# Delay.net
KiCad netlist of a schematic drawn in Altium Designer
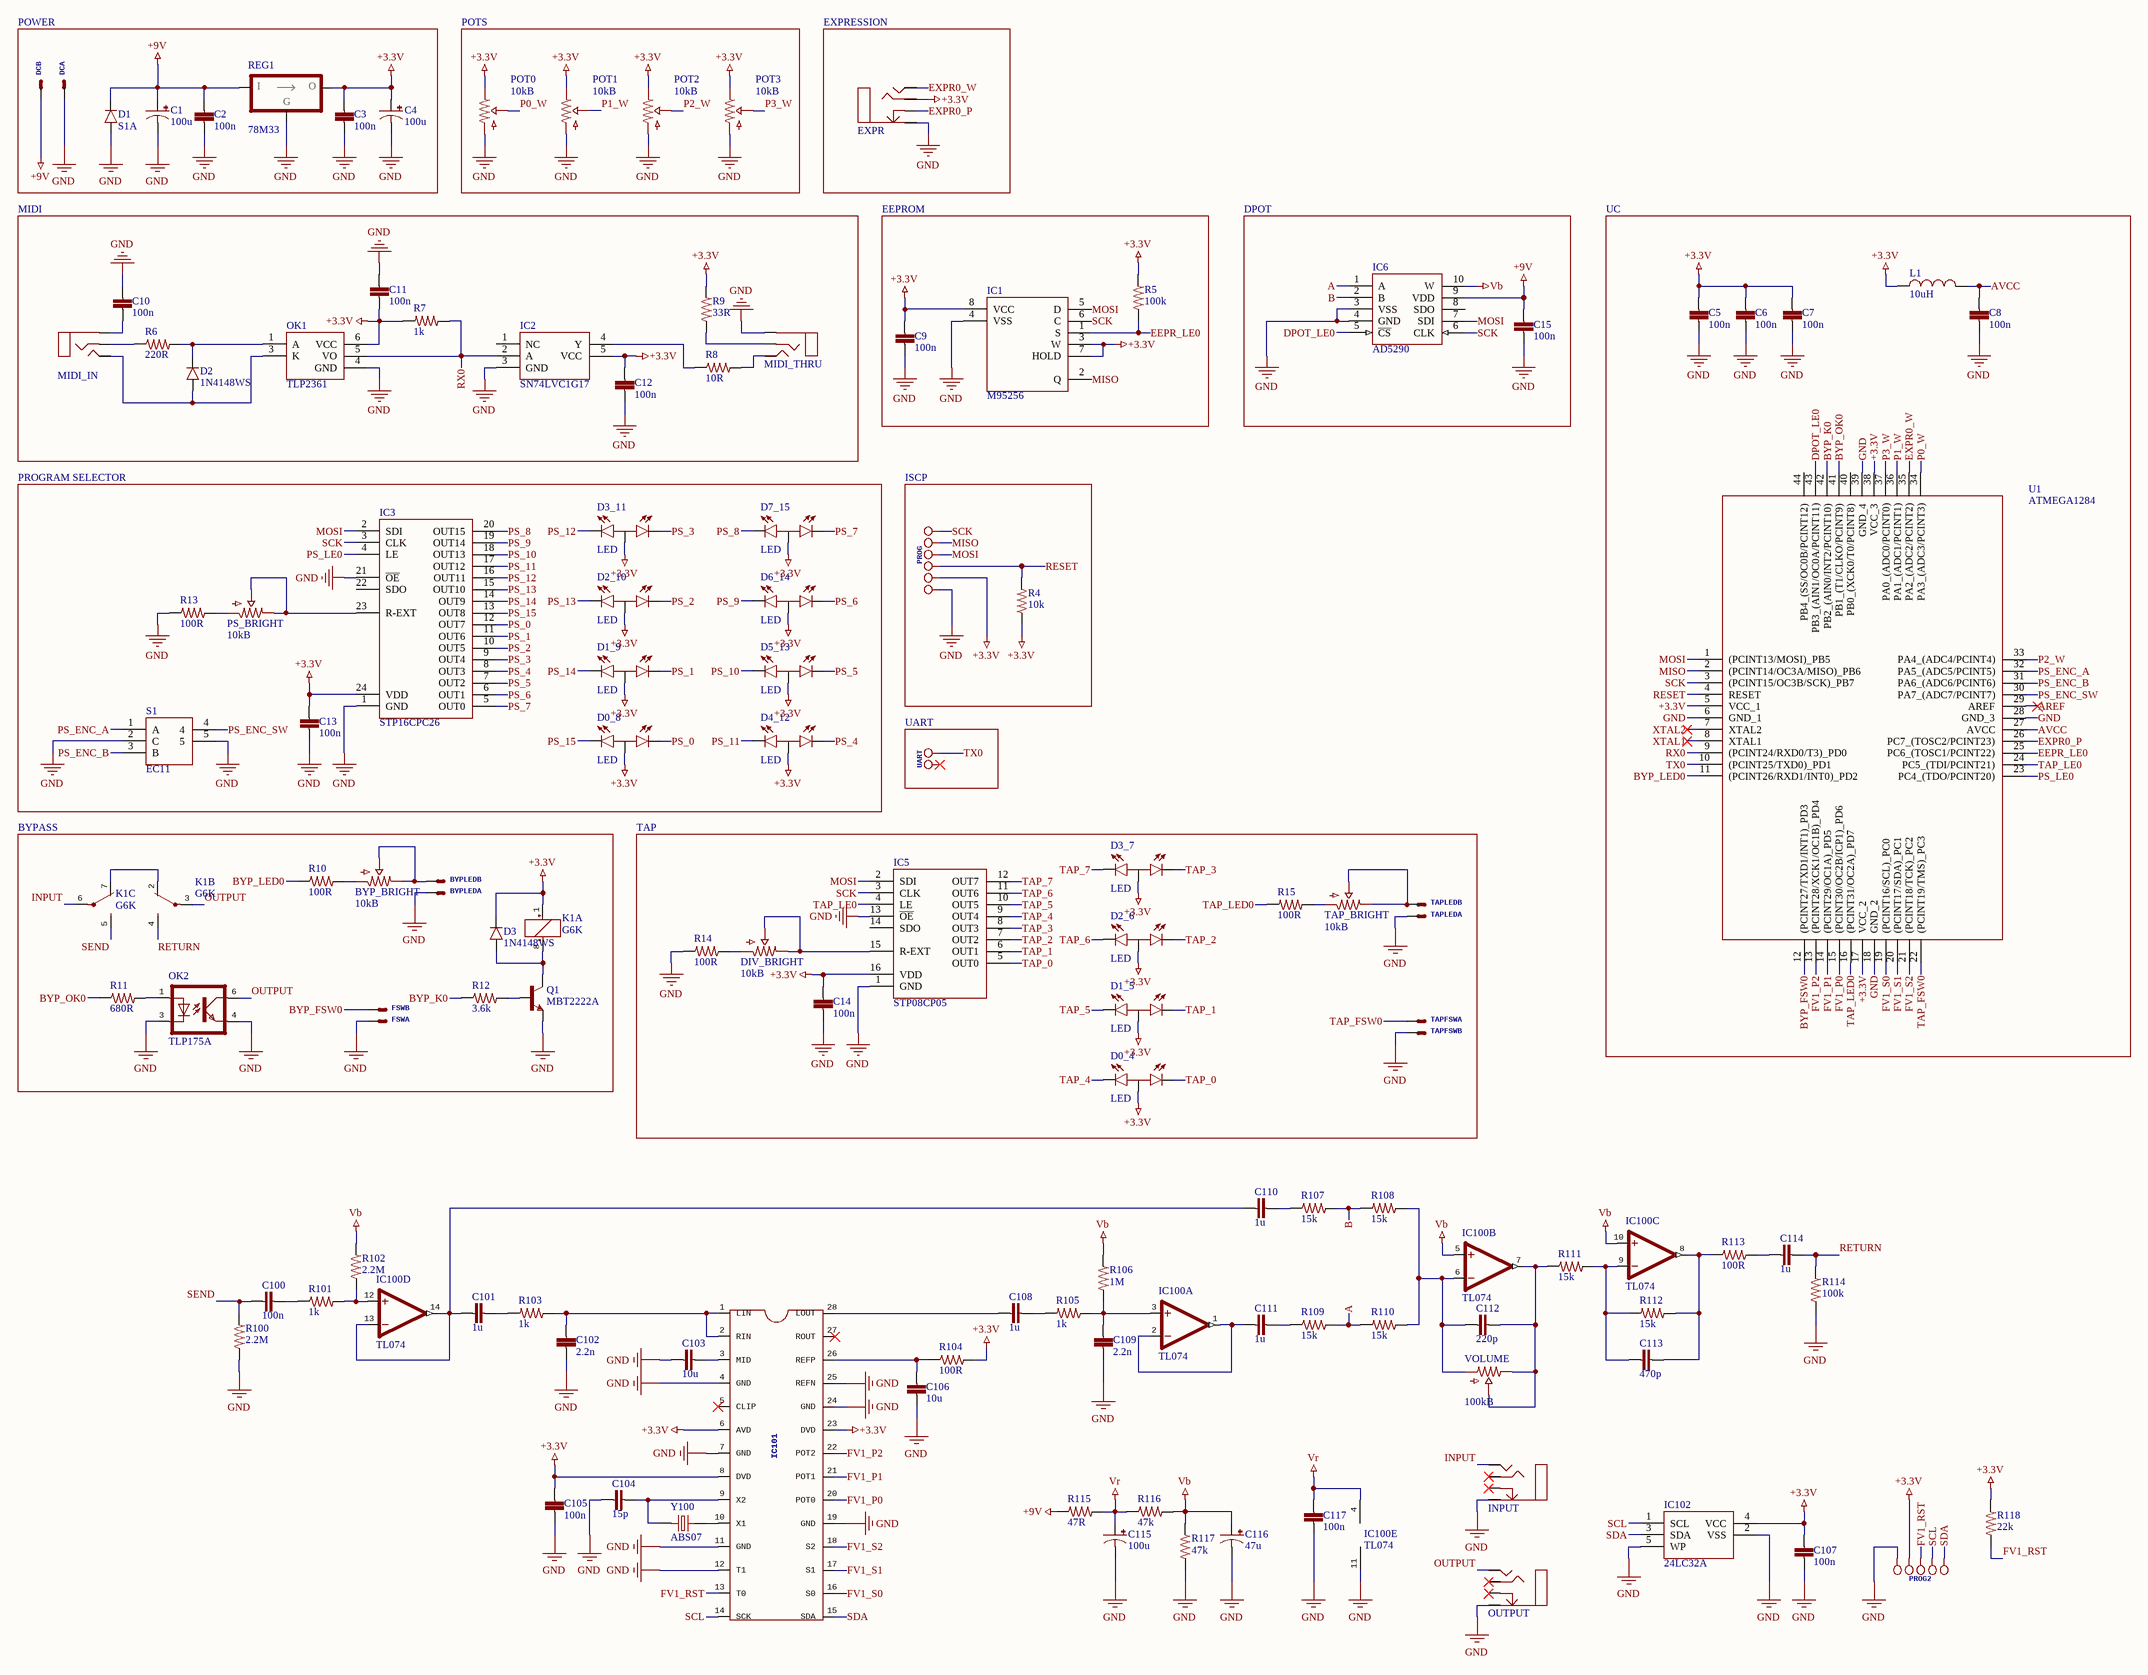
[diagram p0: Delay.SchDoc]

(export (version "E")
  (design (tool "Eeschema 10.0.6"))
  (components
    (comp (ref "BYPLED")
      (value "~")
      (footprint "JST-XH-02")
      (description "2 Pins male XH header")
      (libsource (lib "Pedals") (part "JST-XH-02"))
    )
    (comp (ref "BYP_BRIGHT")
      (value "10kB")
      (footprint "BOURNS_3362P")
      (description "10k Lin 3362P trimmer")
      (libsource (lib "Pedals") (part "TRIM_10kB_3362P"))
    )
    (comp (ref "C1")
      (value "100u")
      (footprint "CAPAE_D")
      (description "CAP ALUM 100UF 25V SMD")
      (fields
        (field (name "MANUFACTURER") "Multicomp")
        (field (name "MANUFACTURER PART NUMBER") "MCVVT025M101EA6L")
      )
      (libsource (lib "Pedals SMD") (part "MCVVT025M101EA6L"))
    )
    (comp (ref "C2")
      (value "100n")
      (footprint "CHIP_0603")
      (description "CAP CER 100NF 50V X7R 0603")
      (fields
        (field (name "MANUFACTURER") "Multicomp")
        (field (name "MANUFACTURER PART NUMBER") "MC0603B104K500CT")
      )
      (libsource (lib "") (part "MC0603B104K500CT_2"))
    )
    (comp (ref "C3")
      (value "100n")
      (footprint "CHIP_0603")
      (description "CAP CER 100NF 50V X7R 0603")
      (fields
        (field (name "MANUFACTURER") "Multicomp")
        (field (name "MANUFACTURER PART NUMBER") "MC0603B104K500CT")
      )
      (libsource (lib "Pedals SMD") (part "MC0603B104K500CT"))
    )
    (comp (ref "C4")
      (value "100u")
      (footprint "CAPAE_D")
      (description "CAP ALUM 100UF 25V SMD")
      (fields
        (field (name "MANUFACTURER") "Multicomp")
        (field (name "MANUFACTURER PART NUMBER") "MCVVT025M101EA6L")
      )
      (libsource (lib "Pedals SMD") (part "MCVVT025M101EA6L"))
    )
    (comp (ref "C5")
      (value "100n")
      (footprint "CHIP_0603")
      (description "CAP CER 100NF 50V X7R 0603")
      (fields
        (field (name "MANUFACTURER") "Multicomp")
        (field (name "MANUFACTURER PART NUMBER") "MC0603B104K500CT")
      )
      (libsource (lib "Pedals SMD") (part "MC0603B104K500CT"))
    )
    (comp (ref "C6")
      (value "100n")
      (footprint "CHIP_0603")
      (description "CAP CER 100NF 50V X7R 0603")
      (fields
        (field (name "MANUFACTURER") "Multicomp")
        (field (name "MANUFACTURER PART NUMBER") "MC0603B104K500CT")
      )
      (libsource (lib "Pedals SMD") (part "MC0603B104K500CT"))
    )
    (comp (ref "C7")
      (value "100n")
      (footprint "CHIP_0603")
      (description "CAP CER 100NF 50V X7R 0603")
      (fields
        (field (name "MANUFACTURER") "Multicomp")
        (field (name "MANUFACTURER PART NUMBER") "MC0603B104K500CT")
      )
      (libsource (lib "Pedals SMD") (part "MC0603B104K500CT"))
    )
    (comp (ref "C8")
      (value "100n")
      (footprint "CHIP_0603")
      (description "CAP CER 100NF 50V X7R 0603")
      (fields
        (field (name "MANUFACTURER") "Multicomp")
        (field (name "MANUFACTURER PART NUMBER") "MC0603B104K500CT")
      )
      (libsource (lib "Pedals SMD") (part "MC0603B104K500CT"))
    )
    (comp (ref "C9")
      (value "100n")
      (footprint "CHIP_0603")
      (description "CAP CER 100NF 50V X7R 0603")
      (fields
        (field (name "MANUFACTURER") "Multicomp")
        (field (name "MANUFACTURER PART NUMBER") "MC0603B104K500CT")
      )
      (libsource (lib "") (part "MC0603B104K500CT_1"))
    )
    (comp (ref "C10")
      (value "100n")
      (footprint "CHIP_0603")
      (description "CAP CER 100NF 50V X7R 0603")
      (fields
        (field (name "MANUFACTURER") "Multicomp")
        (field (name "MANUFACTURER PART NUMBER") "MC0603B104K500CT")
      )
      (libsource (lib "") (part "MC0603B104K500CT_1"))
    )
    (comp (ref "C11")
      (value "100n")
      (footprint "CHIP_0603")
      (description "CAP CER 100NF 50V X7R 0603")
      (fields
        (field (name "MANUFACTURER") "Multicomp")
        (field (name "MANUFACTURER PART NUMBER") "MC0603B104K500CT")
      )
      (libsource (lib "") (part "MC0603B104K500CT_1"))
    )
    (comp (ref "C12")
      (value "100n")
      (footprint "CHIP_0603")
      (description "CAP CER 100NF 50V X7R 0603")
      (fields
        (field (name "MANUFACTURER") "Multicomp")
        (field (name "MANUFACTURER PART NUMBER") "MC0603B104K500CT")
      )
      (libsource (lib "") (part "MC0603B104K500CT_1"))
    )
    (comp (ref "C13")
      (value "100n")
      (footprint "CHIP_0603")
      (description "CAP CER 100NF 50V X7R 0603")
      (fields
        (field (name "MANUFACTURER") "Multicomp")
        (field (name "MANUFACTURER PART NUMBER") "MC0603B104K500CT")
      )
      (libsource (lib "Pedals SMD") (part "MC0603B104K500CT"))
    )
    (comp (ref "C14")
      (value "100n")
      (footprint "CHIP_0603")
      (description "CAP CER 100NF 50V X7R 0603")
      (fields
        (field (name "MANUFACTURER") "Multicomp")
        (field (name "MANUFACTURER PART NUMBER") "MC0603B104K500CT")
      )
      (libsource (lib "Pedals SMD") (part "MC0603B104K500CT"))
    )
    (comp (ref "C15")
      (value "100n")
      (footprint "CHIP_0603")
      (description "CAP CER 100NF 50V X7R 0603")
      (fields
        (field (name "MANUFACTURER") "Multicomp")
        (field (name "MANUFACTURER PART NUMBER") "MC0603B104K500CT")
      )
      (libsource (lib "Pedals SMD") (part "MC0603B104K500CT"))
    )
    (comp (ref "C100")
      (value "100n")
      (footprint "CHIP_1206")
      (description "CAP CER 100NF 50V C0G/NP0 1206")
      (fields
        (field (name "MANUFACTURER") "Murata")
        (field (name "MANUFACTURER PART NUMBER") "GRM31C5C1H104JA01L")
      )
      (libsource (lib "Pedals SMD") (part "GRM31C5C1H104JA01L"))
    )
    (comp (ref "C101")
      (value "1u")
      (footprint "CHIP_1210")
      (description "CAP FILM 1UF 16V 20%")
      (fields
        (field (name "MANUFACTURER") "Panasonic")
        (field (name "MANUFACTURER PART NUMBER") "ECP-U1C105MA5")
      )
      (libsource (lib "Pedals SMD") (part "ECP-U1C105MA5"))
    )
    (comp (ref "C102")
      (value "2.2n")
      (footprint "CHIP_0603")
      (description "CAP CER 2.2NF 50V C0G/NP0 0603")
      (fields
        (field (name "MANUFACTURER") "Murata")
        (field (name "MANUFACTURER PART NUMBER") "GRM1885C1H222JA01D")
      )
      (libsource (lib "Pedals SMD") (part "GRM1885C1H222JA01D"))
    )
    (comp (ref "C103")
      (value "10u")
      (footprint "CHIP_1206")
      (description "CAP CER 10uF 25V X7R 1206")
      (fields
        (field (name "MANUFACTURER") "Taiyo Yuden")
        (field (name "MANUFACTURER PART NUMBER") "TMK316B7106KL-TD")
      )
      (libsource (lib "Pedals SMD") (part "TMK316B7106KL-TD"))
    )
    (comp (ref "C104")
      (value "15p")
      (footprint "CHIP_0603")
      (description "CAP CER 15PF 50V C0G/NP0 0603")
      (fields
        (field (name "MANUFACTURER") "Multicomp")
        (field (name "MANUFACTURER PART NUMBER") "MC0603N150J500CT")
      )
      (libsource (lib "Pedals SMD") (part "MC0603N150J500CT"))
    )
    (comp (ref "C105")
      (value "100n")
      (footprint "CHIP_0603")
      (description "CAP CER 100NF 50V X7R 0603")
      (fields
        (field (name "MANUFACTURER") "Multicomp")
        (field (name "MANUFACTURER PART NUMBER") "MC0603B104K500CT")
      )
      (libsource (lib "Pedals SMD") (part "MC0603B104K500CT"))
    )
    (comp (ref "C106")
      (value "10u")
      (footprint "CHIP_1206")
      (description "CAP CER 10uF 25V X7R 1206")
      (fields
        (field (name "MANUFACTURER") "Taiyo Yuden")
        (field (name "MANUFACTURER PART NUMBER") "TMK316B7106KL-TD")
      )
      (libsource (lib "") (part "TMK316B7106KL-TD_1"))
    )
    (comp (ref "C107")
      (value "100n")
      (footprint "CHIP_0603")
      (description "CAP CER 100NF 50V X7R 0603")
      (fields
        (field (name "MANUFACTURER") "Multicomp")
        (field (name "MANUFACTURER PART NUMBER") "MC0603B104K500CT")
      )
      (libsource (lib "Pedals SMD") (part "MC0603B104K500CT"))
    )
    (comp (ref "C108")
      (value "1u")
      (footprint "CHIP_1210")
      (description "CAP FILM 1UF 16V 20%")
      (fields
        (field (name "MANUFACTURER") "Panasonic")
        (field (name "MANUFACTURER PART NUMBER") "ECP-U1C105MA5")
      )
      (libsource (lib "Pedals SMD") (part "ECP-U1C105MA5"))
    )
    (comp (ref "C109")
      (value "2.2n")
      (footprint "CHIP_0603")
      (description "CAP CER 2.2NF 50V C0G/NP0 0603")
      (fields
        (field (name "MANUFACTURER") "Murata")
        (field (name "MANUFACTURER PART NUMBER") "GRM1885C1H222JA01D")
      )
      (libsource (lib "Pedals SMD") (part "GRM1885C1H222JA01D"))
    )
    (comp (ref "C110")
      (value "1u")
      (footprint "CHIP_1210")
      (description "CAP FILM 1UF 16V 20%")
      (fields
        (field (name "MANUFACTURER") "Panasonic")
        (field (name "MANUFACTURER PART NUMBER") "ECP-U1C105MA5")
      )
      (libsource (lib "Pedals SMD") (part "ECP-U1C105MA5"))
    )
    (comp (ref "C111")
      (value "1u")
      (footprint "CHIP_1210")
      (description "CAP FILM 1UF 16V 20%")
      (fields
        (field (name "MANUFACTURER") "Panasonic")
        (field (name "MANUFACTURER PART NUMBER") "ECP-U1C105MA5")
      )
      (libsource (lib "Pedals SMD") (part "ECP-U1C105MA5"))
    )
    (comp (ref "C112")
      (value "220p")
      (footprint "CHIP_0603")
      (description "CAP CER 220PF 50V C0G/NP0 0603")
      (fields
        (field (name "MANUFACTURER") "Multicomp")
        (field (name "MANUFACTURER PART NUMBER") "MC0603N221J500CT")
      )
      (libsource (lib "Pedals SMD") (part "MC0603N221J500CT"))
    )
    (comp (ref "C113")
      (value "470p")
      (footprint "CHIP_0603")
      (description "CAP CER 470PF 50V C0G/NP0 0603")
      (fields
        (field (name "MANUFACTURER") "Multicomp")
        (field (name "MANUFACTURER PART NUMBER") "MC0603N471J500CT")
      )
      (libsource (lib "Pedals SMD") (part "MC0603N471J500CT"))
    )
    (comp (ref "C114")
      (value "1u")
      (footprint "CHIP_1210")
      (description "CAP FILM 1UF 16V 20%")
      (fields
        (field (name "MANUFACTURER") "Panasonic")
        (field (name "MANUFACTURER PART NUMBER") "ECP-U1C105MA5")
      )
      (libsource (lib "Pedals SMD") (part "ECP-U1C105MA5"))
    )
    (comp (ref "C115")
      (value "100u")
      (footprint "CAPAE_D")
      (description "CAP ALUM 100UF 25V SMD")
      (fields
        (field (name "MANUFACTURER") "Multicomp")
        (field (name "MANUFACTURER PART NUMBER") "MCVVT025M101EA6L")
      )
      (libsource (lib "Pedals SMD") (part "MCVVT025M101EA6L"))
    )
    (comp (ref "C116")
      (value "47u")
      (footprint "CAPAE_D")
      (description "CAP ALUM 47UF 25V SMD")
      (fields
        (field (name "MANUFACTURER") "Multicomp")
        (field (name "MANUFACTURER PART NUMBER") "MCVVT025M470EA1L")
      )
      (libsource (lib "Pedals SMD") (part "MCVVT025M470EA1L"))
    )
    (comp (ref "C117")
      (value "100n")
      (footprint "CHIP_0603")
      (description "CAP CER 100NF 50V X7R 0603")
      (fields
        (field (name "MANUFACTURER") "Multicomp")
        (field (name "MANUFACTURER PART NUMBER") "MC0603B104K500CT")
      )
      (libsource (lib "Pedals SMD") (part "MC0603B104K500CT"))
    )
    (comp (ref "D0_4")
      (value "LED")
      (footprint "LED_3MM_BICOLOR")
      (description "BICOLOR LED")
      (libsource (lib "Pedals") (part "D_BICOLOR_LED"))
    )
    (comp (ref "D0_8")
      (value "LED")
      (footprint "LED_3MM_BICOLOR")
      (description "BICOLOR LED")
      (libsource (lib "Pedals") (part "D_BICOLOR_LED"))
    )
    (comp (ref "D1")
      (value "S1A")
      (footprint "DO214")
      (description "DIODE GEN PURP 50V 1A SMA")
      (fields (field (name "MANUFACTURER") "ON Semiconductor / Fairchild"))
      (libsource (lib "Pedals SMD") (part "S1A"))
    )
    (comp (ref "D1_5")
      (value "LED")
      (footprint "LED_3MM_BICOLOR")
      (description "BICOLOR LED")
      (libsource (lib "Pedals") (part "D_BICOLOR_LED"))
    )
    (comp (ref "D1_9")
      (value "LED")
      (footprint "LED_3MM_BICOLOR")
      (description "BICOLOR LED")
      (libsource (lib "Pedals") (part "D_BICOLOR_LED"))
    )
    (comp (ref "D2")
      (value "1N4148WS")
      (footprint "SOD323")
      (description "DIODE GEN PURP 75V 150MA SOD323F")
      (fields (field (name "MANUFACTURER") "ON Semiconductor / Fairchild"))
      (libsource (lib "Pedals SMD") (part "1N4148WS"))
    )
    (comp (ref "D2_6")
      (value "LED")
      (footprint "LED_3MM_BICOLOR")
      (description "BICOLOR LED")
      (libsource (lib "Pedals") (part "D_BICOLOR_LED"))
    )
    (comp (ref "D2_10")
      (value "LED")
      (footprint "LED_3MM_BICOLOR")
      (description "BICOLOR LED")
      (libsource (lib "Pedals") (part "D_BICOLOR_LED"))
    )
    (comp (ref "D3")
      (value "1N4148WS")
      (footprint "SOD323")
      (description "DIODE GEN PURP 75V 150MA SOD323F")
      (fields (field (name "MANUFACTURER") "ON Semiconductor / Fairchild"))
      (libsource (lib "Pedals SMD") (part "1N4148WS"))
    )
    (comp (ref "D3_7")
      (value "LED")
      (footprint "LED_3MM_BICOLOR")
      (description "BICOLOR LED")
      (libsource (lib "Pedals") (part "D_BICOLOR_LED"))
    )
    (comp (ref "D3_11")
      (value "LED")
      (footprint "LED_3MM_BICOLOR")
      (description "BICOLOR LED")
      (libsource (lib "Pedals") (part "D_BICOLOR_LED"))
    )
    (comp (ref "D4_12")
      (value "LED")
      (footprint "LED_3MM_BICOLOR")
      (description "BICOLOR LED")
      (libsource (lib "Pedals") (part "D_BICOLOR_LED"))
    )
    (comp (ref "D5_13")
      (value "LED")
      (footprint "LED_3MM_BICOLOR")
      (description "BICOLOR LED")
      (libsource (lib "Pedals") (part "D_BICOLOR_LED"))
    )
    (comp (ref "D6_14")
      (value "LED")
      (footprint "LED_3MM_BICOLOR")
      (description "BICOLOR LED")
      (libsource (lib "Pedals") (part "D_BICOLOR_LED"))
    )
    (comp (ref "D7_15")
      (value "LED")
      (footprint "LED_3MM_BICOLOR")
      (description "BICOLOR LED")
      (libsource (lib "Pedals") (part "D_BICOLOR_LED"))
    )
    (comp (ref "DC")
      (value "J_JST-XH-02")
      (footprint "JST-XH-02")
      (description "2 Pins male XH header")
      (libsource (lib "Pedals") (part "J_JST-XH-02"))
    )
    (comp (ref "DIV_BRIGHT")
      (value "10kB")
      (footprint "BOURNS_3362P")
      (description "10k Lin 3362P trimmer")
      (libsource (lib "Pedals") (part "TRIM_10kB_3362P"))
    )
    (comp (ref "EXPR")
      (value "J_STEREO")
      (footprint "STEREO")
      (description "6.35mm stereo insulated socket jack PCB mounted")
      (libsource (lib "Pedals") (part "J_STEREO"))
    )
    (comp (ref "FSW")
      (value "~")
      (footprint "JST-XH-02")
      (description "2 Pins male XH header")
      (libsource (lib "Pedals") (part "JST-XH-02"))
    )
    (comp (ref "IC1")
      (value "M95256")
      (footprint "SO-8")
      (description "IC EEPROM 256K SPI 20MHZ 8SO")
      (fields
        (field (name "MANUFACTURER") "STMicroelectronics")
        (field (name "MANUFACTURER PART NUMBER") "M95256-WMN6P")
      )
      (libsource (lib "Pedals SMD") (part "M95256-WMN6P"))
    )
    (comp (ref "IC2")
      (value "SN74LVC1G17")
      (footprint "SOT-23-5")
      (description "Schmitt Trigger Buffer 1-CH Non-Inverting CMOS Automotive 5-Pin SOT-23 T/R")
      (fields
        (field (name "MANUFACTURER") "Texas Instruments")
        (field (name "MANUFACTURER PART NUMBER") "SN74LVC1G17QDBVRQ1")
      )
      (libsource (lib "Pedals SMD") (part "SN74LVC1G17QDBVRQ1"))
    )
    (comp (ref "IC3")
      (value "STP16CPC26")
      (footprint "SO-24")
      (description "IC LED DRIVER LIN DIM 90MA 24SO")
      (fields
        (field (name "MANUFACTURER") "STMicroelectronics")
        (field (name "MANUFACTURER PART NUMBER") "STP16CPC26MTR")
      )
      (libsource (lib "Pedals SMD") (part "STP16CPC26MTR"))
    )
    (comp (ref "IC5")
      (value "STP08CP05")
      (footprint "SO-16")
      (description "IC SHIFT REGISTER 8BIT 16SOIC")
      (fields
        (field (name "MANUFACTURER") "STMicroelectronics")
        (field (name "MANUFACTURER PART NUMBER") "STP08CP05MTR")
      )
      (libsource (lib "Pedals SMD") (part "STP08CP05MTR"))
    )
    (comp (ref "IC6")
      (value "AD5290")
      (footprint "MSOP-10")
      (description "DIGIPOT 8BIT 10K, SMD, 5290, MSOP10")
      (fields
        (field (name "MANUFACTURER") "Analog Devices")
        (field (name "MANUFACTURER PART NUMBER") "AD5290YRMZ10")
      )
      (libsource (lib "Pedals SMD") (part "AD5290YRMZ10"))
    )
    (comp (ref "IC100")
      (value "TL074")
      (footprint "SO-14")
      (description "IC OPAMP JFET 3MHZ 14SO")
      (fields
        (field (name "MANUFACTURER") "STMicroelectronics")
        (field (name "MANUFACTURER PART NUMBER") "TL074IDT")
      )
      (libsource (lib "Pedals SMD") (part "TL074IDT"))
    )
    (comp (ref "IC101")
      (value "FV-1")
      (footprint "SO-28")
      (description "Spinsemi FV-1")
      (libsource (lib "Pedals SMD") (part "FV-1"))
    )
    (comp (ref "IC102")
      (value "24LC32A")
      (footprint "SOT-23-5")
      (description "IC EEPROM 32KBIT 400KHZ SOT23-5")
      (fields
        (field (name "MANUFACTURER") "Microchip")
        (field (name "MANUFACTURER PART NUMBER") "24LC32AT-I/OT")
      )
      (libsource (lib "Pedals SMD") (part "24LC32AT-I/OT"))
    )
    (comp (ref "INPUT")
      (value "J_STEREO")
      (footprint "STEREO")
      (description "6.35mm stereo insulated socket jack PCB mounted")
      (libsource (lib "Pedals") (part "J_STEREO"))
    )
    (comp (ref "K1")
      (value "G6K")
      (footprint "G6K")
      (description "OMRON ELECTRONIC COMPONENTS   G6K-2F 3DC   RELAY, SMD, DPCO, 3VDC")
      (fields (field (name "MANUFACTURER") "Omron") (field (name "MANUFACTURER PART NUMBER") "G6K2F3DC"))
      (libsource (lib "Pedals SMD") (part "G6K2F3DC"))
    )
    (comp (ref "L1")
      (value "10uH")
      (footprint "INDC1608X10")
      (fields
        (field (name "MANUFACTURER") "TDK")
        (field (name "MANUFACTURER PART NUMBER") "MLZ1608N100LT")
        (field (name "TOLERANCE") "20%")
      )
      (libsource (lib "Pedals SMD") (part "MLZ1608N100LT"))
    )
    (comp (ref "MIDI_IN")
      (value "J_STEREO_3.5")
      (footprint "STEREO_3.5")
      (description "3.5mm stereo socket jack PCB mounted")
      (libsource (lib "Pedals") (part "J_STEREO_3.5"))
    )
    (comp (ref "MIDI_THRU")
      (value "J_STEREO_3.5")
      (footprint "STEREO_3.5")
      (description "3.5mm stereo socket jack PCB mounted")
      (libsource (lib "Pedals") (part "J_STEREO_3.5"))
    )
    (comp (ref "OK1")
      (value "TLP2361")
      (footprint "TLP2361")
      (description "TOSHIBA - TLP2361 - OPTOKOPPLER, DIGITAL, 3.75KV, SOP-5")
      (fields (field (name "MANUFACTURER") "Toshiba"))
      (libsource (lib "Pedals SMD") (part "TLP2361"))
    )
    (comp (ref "OK2")
      (value "TLP175A")
      (footprint "TLP175A")
      (description "Toshiba TLP175A AC Input MOSFET Output Optocoupler, Surface Mount, 4-Pin SOIC")
      (fields (field (name "MANUFACTURER") "Toshiba"))
      (libsource (lib "Pedals SMD") (part "TLP175A"))
    )
    (comp (ref "OUTPUT")
      (value "J_STEREO")
      (footprint "STEREO")
      (description "6.35mm stereo insulated socket jack PCB mounted")
      (libsource (lib "Pedals") (part "J_STEREO"))
    )
    (comp (ref "POT0")
      (value "10kB")
      (footprint "ALPHA_9MM_TOP_NOMH")
      (description "10k Lin potentiometer round shaft")
      (libsource (lib "Pedals") (part "POT_10kB_ALPHA_9mm"))
    )
    (comp (ref "POT1")
      (value "10kB")
      (footprint "ALPHA_9MM_TOP_NOMH")
      (description "10k Lin potentiometer round shaft")
      (libsource (lib "Pedals") (part "POT_10kB_ALPHA_9mm"))
    )
    (comp (ref "POT2")
      (value "10kB")
      (footprint "ALPHA_9MM_TOP_NOMH")
      (description "10k Lin potentiometer round shaft")
      (libsource (lib "Pedals") (part "POT_10kB_ALPHA_9mm"))
    )
    (comp (ref "POT3")
      (value "10kB")
      (footprint "ALPHA_9MM_TOP_NOMH")
      (description "10k Lin potentiometer round shaft")
      (libsource (lib "Pedals") (part "POT_10kB_ALPHA_9mm"))
    )
    (comp (ref "PROG")
      (value "J_HEADER_6PINS_FEM")
      (footprint "HEADER_6Pins_FEM")
      (description "5 Pins female header")
      (libsource (lib "Pedals") (part "J_HEADER_6PINS_FEM"))
    )
    (comp (ref "PROG2")
      (value "J_HEADER_5PINS_FEM")
      (footprint "HEADER_5Pins_FEM")
      (description "5 Pins female header")
      (libsource (lib "Pedals") (part "J_HEADER_5PINS_FEM"))
    )
    (comp (ref "PS_BRIGHT")
      (value "10kB")
      (footprint "BOURNS_3362P")
      (description "10k Lin 3362P trimmer")
      (libsource (lib "Pedals") (part "TRIM_10kB_3362P"))
    )
    (comp (ref "Q1")
      (value "MBT2222A")
      (footprint "SOT323")
      (description "TRANS NPN 40V 0.6A SOT323")
      (fields
        (field (name "MANUFACTURER") "ON Semiconductor")
        (field (name "MANUFACTURER PART NUMBER") "MMBT2222AWT1G")
      )
      (libsource (lib "Pedals SMD") (part "MMBT2222AWT1G"))
    )
    (comp (ref "R4")
      (value "10k")
      (footprint "CHIP_R_0603")
      (description "RES SMD 10K OHM 1% 1/10W 0603")
      (fields
        (field (name "MANUFACTURER") "Vishay")
        (field (name "MANUFACTURER PART NUMBER") "CRCW060310K0FKEA")
      )
      (libsource (lib "Pedals SMD") (part "CRCW060310K0FKEA"))
    )
    (comp (ref "R5")
      (value "100k")
      (footprint "CHIP_R_0603")
      (description "RES SMD 100K OHM 1% 1/10W 0603")
      (fields
        (field (name "MANUFACTURER") "Vishay")
        (field (name "MANUFACTURER PART NUMBER") "CRCW0603100KFKEA")
      )
      (libsource (lib "Pedals SMD") (part "CRCW0603100KFKEA"))
    )
    (comp (ref "R6")
      (value "220R")
      (footprint "CHIP_R_0603")
      (description "RES SMD 220 OHM 1% 1/10W 0603")
      (fields
        (field (name "MANUFACTURER") "Vishay")
        (field (name "MANUFACTURER PART NUMBER") "CRCW0603220RFKEA")
      )
      (libsource (lib "Pedals SMD") (part "CRCW0603220RFKEA"))
    )
    (comp (ref "R7")
      (value "1k")
      (footprint "CHIP_R_0603")
      (description "RES SMD 1K OHM 1% 1/10W 0603")
      (fields
        (field (name "MANUFACTURER") "Vishay Dale")
        (field (name "MANUFACTURER PART NUMBER") "CRCW06031K00FKEA")
      )
      (libsource (lib "Pedals SMD") (part "CRCW06031K00FKEA"))
    )
    (comp (ref "R8")
      (value "10R")
      (footprint "CHIP_R_0603")
      (description "RES SMD 10 OHM 1% 1/10W 0603")
      (fields
        (field (name "MANUFACTURER") "Vishay")
        (field (name "MANUFACTURER PART NUMBER") "CRCW060310R0FKEA")
      )
      (libsource (lib "Pedals SMD") (part "CRCW060310R0FKEA"))
    )
    (comp (ref "R9")
      (value "33R")
      (footprint "CHIP_R_0603")
      (description "RES SMD 33 OHM 1% 1/10W 0603")
      (fields
        (field (name "MANUFACTURER") "Vishay")
        (field (name "MANUFACTURER PART NUMBER") "CRCW060333R0FKEA")
      )
      (libsource (lib "Pedals SMD") (part "CRCW060333R0FKEA"))
    )
    (comp (ref "R10")
      (value "100R")
      (footprint "CHIP_R_1206")
      (description "RES SMD 100 OHM 1% 1/4W 1206")
      (fields
        (field (name "MANUFACTURER") "Vishay Dale")
        (field (name "MANUFACTURER PART NUMBER") "CRCW1206100RFKEA")
      )
      (libsource (lib "Pedals SMD") (part "CRCW1206100RFKEA"))
    )
    (comp (ref "R11")
      (value "680R")
      (footprint "CHIP_R_0603")
      (description "RES SMD 680R OHM 1% 1/10W 0603")
      (fields
        (field (name "MANUFACTURER") "Vishay")
        (field (name "MANUFACTURER PART NUMBER") "CRCW0603680RFKEA")
      )
      (libsource (lib "Pedals SMD") (part "CRCW0603680RFKEA"))
    )
    (comp (ref "R12")
      (value "3.6k")
      (footprint "CHIP_R_0603")
      (description "RES SMD 3.6K OHM 1% 1/10W 0603")
      (fields
        (field (name "MANUFACTURER") "Vishay")
        (field (name "MANUFACTURER PART NUMBER") "CRCW06033K60FKEA")
      )
      (libsource (lib "Pedals SMD") (part "CRCW06033K60FKEA"))
    )
    (comp (ref "R13")
      (value "100R")
      (footprint "CHIP_R_1206")
      (description "RES SMD 100 OHM 1% 1/4W 1206")
      (fields
        (field (name "MANUFACTURER") "Vishay Dale")
        (field (name "MANUFACTURER PART NUMBER") "CRCW1206100RFKEA")
      )
      (libsource (lib "Pedals SMD") (part "CRCW1206100RFKEA"))
    )
    (comp (ref "R14")
      (value "100R")
      (footprint "CHIP_R_1206")
      (description "RES SMD 100 OHM 1% 1/4W 1206")
      (fields
        (field (name "MANUFACTURER") "Vishay Dale")
        (field (name "MANUFACTURER PART NUMBER") "CRCW1206100RFKEA")
      )
      (libsource (lib "Pedals SMD") (part "CRCW1206100RFKEA"))
    )
    (comp (ref "R15")
      (value "100R")
      (footprint "CHIP_R_1206")
      (description "RES SMD 100 OHM 1% 1/4W 1206")
      (fields
        (field (name "MANUFACTURER") "Vishay Dale")
        (field (name "MANUFACTURER PART NUMBER") "CRCW1206100RFKEA")
      )
      (libsource (lib "Pedals SMD") (part "CRCW1206100RFKEA"))
    )
    (comp (ref "R100")
      (value "2.2M")
      (footprint "CHIP_R_0603")
      (description "RES SMD 2.2M OHM 1% 1/10W 0603")
      (fields
        (field (name "MANUFACTURER") "Vishay")
        (field (name "MANUFACTURER PART NUMBER") "CRCW06032M20FKEA")
      )
      (libsource (lib "Pedals SMD") (part "CRCW06032M20FKEA"))
    )
    (comp (ref "R101")
      (value "1k")
      (footprint "CHIP_R_0603")
      (description "RES SMD 1K OHM 1% 1/10W 0603")
      (fields
        (field (name "MANUFACTURER") "Vishay Dale")
        (field (name "MANUFACTURER PART NUMBER") "CRCW06031K00FKEA")
      )
      (libsource (lib "Pedals SMD") (part "CRCW06031K00FKEA"))
    )
    (comp (ref "R102")
      (value "2.2M")
      (footprint "CHIP_R_0603")
      (description "RES SMD 2.2M OHM 1% 1/10W 0603")
      (fields
        (field (name "MANUFACTURER") "Vishay")
        (field (name "MANUFACTURER PART NUMBER") "CRCW06032M20FKEA")
      )
      (libsource (lib "Pedals SMD") (part "CRCW06032M20FKEA"))
    )
    (comp (ref "R103")
      (value "1k")
      (footprint "CHIP_R_0603")
      (description "RES SMD 1K OHM 1% 1/10W 0603")
      (fields
        (field (name "MANUFACTURER") "Vishay Dale")
        (field (name "MANUFACTURER PART NUMBER") "CRCW06031K00FKEA")
      )
      (libsource (lib "Pedals SMD") (part "CRCW06031K00FKEA"))
    )
    (comp (ref "R104")
      (value "100R")
      (footprint "CHIP_R_0603")
      (description "RES SMD 100 OHM 1% 1/10W 0603")
      (fields
        (field (name "MANUFACTURER") "Vishay Dale")
        (field (name "MANUFACTURER PART NUMBER") "CRCW0603100RFKEA")
      )
      (libsource (lib "Pedals SMD") (part "CRCW0603100RFKEA"))
    )
    (comp (ref "R105")
      (value "1k")
      (footprint "CHIP_R_0603")
      (description "RES SMD 1K OHM 1% 1/10W 0603")
      (fields
        (field (name "MANUFACTURER") "Vishay Dale")
        (field (name "MANUFACTURER PART NUMBER") "CRCW06031K00FKEA")
      )
      (libsource (lib "Pedals SMD") (part "CRCW06031K00FKEA"))
    )
    (comp (ref "R106")
      (value "1M")
      (footprint "CHIP_R_0603")
      (description "RES SMD 1M OHM 1% 1/10W 0603")
      (fields
        (field (name "MANUFACTURER") "Vishay")
        (field (name "MANUFACTURER PART NUMBER") "CRCW06031M00FKEA")
      )
      (libsource (lib "Pedals SMD") (part "CRCW06031M00FKEA"))
    )
    (comp (ref "R107")
      (value "15k")
      (footprint "CHIP_R_0603")
      (description "RES SMD 15K OHM 1% 1/10W 0603")
      (fields
        (field (name "MANUFACTURER") "Vishay")
        (field (name "MANUFACTURER PART NUMBER") "CRCW060315K0FKEA")
      )
      (libsource (lib "Pedals SMD") (part "CRCW060315K0FKEA"))
    )
    (comp (ref "R108")
      (value "15k")
      (footprint "CHIP_R_0603")
      (description "RES SMD 15K OHM 1% 1/10W 0603")
      (fields
        (field (name "MANUFACTURER") "Vishay")
        (field (name "MANUFACTURER PART NUMBER") "CRCW060315K0FKEA")
      )
      (libsource (lib "Pedals SMD") (part "CRCW060315K0FKEA"))
    )
    (comp (ref "R109")
      (value "15k")
      (footprint "CHIP_R_0603")
      (description "RES SMD 15K OHM 1% 1/10W 0603")
      (fields
        (field (name "MANUFACTURER") "Vishay")
        (field (name "MANUFACTURER PART NUMBER") "CRCW060315K0FKEA")
      )
      (libsource (lib "Pedals SMD") (part "CRCW060315K0FKEA"))
    )
    (comp (ref "R110")
      (value "15k")
      (footprint "CHIP_R_0603")
      (description "RES SMD 15K OHM 1% 1/10W 0603")
      (fields
        (field (name "MANUFACTURER") "Vishay")
        (field (name "MANUFACTURER PART NUMBER") "CRCW060315K0FKEA")
      )
      (libsource (lib "Pedals SMD") (part "CRCW060315K0FKEA"))
    )
    (comp (ref "R111")
      (value "15k")
      (footprint "CHIP_R_0603")
      (description "RES SMD 15K OHM 1% 1/10W 0603")
      (fields
        (field (name "MANUFACTURER") "Vishay")
        (field (name "MANUFACTURER PART NUMBER") "CRCW060315K0FKEA")
      )
      (libsource (lib "Pedals SMD") (part "CRCW060315K0FKEA"))
    )
    (comp (ref "R112")
      (value "15k")
      (footprint "CHIP_R_0603")
      (description "RES SMD 15K OHM 1% 1/10W 0603")
      (fields
        (field (name "MANUFACTURER") "Vishay")
        (field (name "MANUFACTURER PART NUMBER") "CRCW060315K0FKEA")
      )
      (libsource (lib "Pedals SMD") (part "CRCW060315K0FKEA"))
    )
    (comp (ref "R113")
      (value "100R")
      (footprint "CHIP_R_0603")
      (description "RES SMD 100 OHM 1% 1/10W 0603")
      (fields
        (field (name "MANUFACTURER") "Vishay Dale")
        (field (name "MANUFACTURER PART NUMBER") "CRCW0603100RFKEA")
      )
      (libsource (lib "Pedals SMD") (part "CRCW0603100RFKEA"))
    )
    (comp (ref "R114")
      (value "100k")
      (footprint "CHIP_R_0603")
      (description "RES SMD 100K OHM 1% 1/10W 0603")
      (fields
        (field (name "MANUFACTURER") "Vishay")
        (field (name "MANUFACTURER PART NUMBER") "CRCW0603100KFKEA")
      )
      (libsource (lib "Pedals SMD") (part "CRCW0603100KFKEA"))
    )
    (comp (ref "R115")
      (value "47R")
      (footprint "CHIP_R_1206")
      (description "RES SMD 47 OHM 1% 1/4W 1206")
      (fields
        (field (name "MANUFACTURER") "Vishay")
        (field (name "MANUFACTURER PART NUMBER") "CRCW120647R0FKEA")
      )
      (libsource (lib "Pedals SMD") (part "CRCW120647R0FKEA"))
    )
    (comp (ref "R116")
      (value "47k")
      (footprint "CHIP_R_1206")
      (description "RES SMD 47K OHM 1% 1/4W 1206")
      (fields
        (field (name "MANUFACTURER") "Vishay")
        (field (name "MANUFACTURER PART NUMBER") "CRCW120647K0FKEA")
      )
      (libsource (lib "Pedals SMD") (part "CRCW120647K0FKEA"))
    )
    (comp (ref "R117")
      (value "47k")
      (footprint "CHIP_R_1206")
      (description "RES SMD 47K OHM 1% 1/4W 1206")
      (fields
        (field (name "MANUFACTURER") "Vishay")
        (field (name "MANUFACTURER PART NUMBER") "CRCW120647K0FKEA")
      )
      (libsource (lib "Pedals SMD") (part "CRCW120647K0FKEA"))
    )
    (comp (ref "R118")
      (value "22k")
      (footprint "CHIP_R_0603")
      (description "RES SMD 22K OHM 1% 1/10W 0603")
      (fields
        (field (name "MANUFACTURER") "Vishay")
        (field (name "MANUFACTURER PART NUMBER") "CRCW060322K0FKEA")
      )
      (libsource (lib "Pedals SMD") (part "CRCW060322K0FKEA"))
    )
    (comp (ref "REG1")
      (value "78M33")
      (footprint "SOT223")
      (description "IC REG LIN 3.3V 500MA SOT223-4")
      (fields
        (field (name "MANUFACTURER") "Texas Instruments")
        (field (name "MANUFACTURER PART NUMBER") "UA78M33CDCYR")
      )
      (libsource (lib "Pedals SMD") (part "UA78M33CDCYR"))
    )
    (comp (ref "S1") (value "EC11") (footprint "ALPHA_EC11") (libsource (lib "Pedals") (part "ENC_EC11")))
    (comp (ref "TAPFSW")
      (value "~")
      (footprint "JST-XH-02")
      (description "2 Pins male XH header")
      (libsource (lib "Pedals") (part "JST-XH-02"))
    )
    (comp (ref "TAPLED")
      (value "~")
      (footprint "JST-XH-02")
      (description "2 Pins male XH header")
      (libsource (lib "Pedals") (part "JST-XH-02"))
    )
    (comp (ref "TAP_BRIGHT")
      (value "10kB")
      (footprint "BOURNS_3362P")
      (description "10k Lin 3362P trimmer")
      (libsource (lib "Pedals") (part "TRIM_10kB_3362P"))
    )
    (comp (ref "U1")
      (value "ATMEGA1284")
      (footprint "TQFP44")
      (description "Integrated Circuit")
      (fields (field (name "MANUFACTURER_PART_NUMBER") "ATMEGA1284-AU"))
      (libsource (lib "Pedals SMD") (part "ATMEGA1284-AU"))
    )
    (comp (ref "UART")
      (value "J_HEADER_2PINS_FEM")
      (footprint "HEADER_2Pins_FEM")
      (description "2 Pins female header")
      (libsource (lib "Pedals") (part "J_HEADER_2PINS_FEM"))
    )
    (comp (ref "VOLUME")
      (value "100kB")
      (footprint "ALPHA_9MM_TOP_NOMH")
      (description "100k Lin potentiometer round shaft")
      (libsource (lib "Pedals") (part "POT_100kB_ALPHA_9mm"))
    )
    (comp (ref "Y100")
      (value "ABS07")
      (footprint "ABS-07")
      (description "CRYSTAL 32.7680KHZ 12.5PF SMD")
      (fields
        (field (name "MANUFACTURER") "Abracon")
        (field (name "MANUFACTURER PART NUMBER") "ABS07-32.768KHZ-T")
      )
      (libsource (lib "Pedals SMD") (part "ABS07-32.768KHZ-T"))
    )
  )
  (nets
    (net (code "1") (name "+3.3V") (class "Default")
      (node (ref "C105") (pin "1") (pinfunction "1_1") (pintype "passive"))
      (node (ref "C107") (pin "1") (pinfunction "1_1") (pintype "passive"))
      (node (ref "C11") (pin "1") (pinfunction "1_1") (pintype "passive"))
      (node (ref "C12") (pin "2") (pinfunction "2_2") (pintype "passive"))
      (node (ref "C13") (pin "1") (pinfunction "1_1") (pintype "passive"))
      (node (ref "C14") (pin "1") (pinfunction "1_1") (pintype "passive"))
      (node (ref "C3") (pin "1") (pinfunction "1_1") (pintype "passive"))
      (node (ref "C4") (pin "+") (pinfunction "+_+") (pintype "passive"))
      (node (ref "C5") (pin "1") (pinfunction "1_1") (pintype "passive"))
      (node (ref "C6") (pin "1") (pinfunction "1_1") (pintype "passive"))
      (node (ref "C7") (pin "1") (pinfunction "1_1") (pintype "passive"))
      (node (ref "C9") (pin "2") (pinfunction "2_2") (pintype "passive"))
      (node (ref "D0_4") (pin "2") (pinfunction "2_2") (pintype "passive"))
      (node (ref "D0_8") (pin "2") (pinfunction "2_2") (pintype "passive"))
      (node (ref "D1_5") (pin "2") (pinfunction "2_2") (pintype "passive"))
      (node (ref "D1_9") (pin "2") (pinfunction "2_2") (pintype "passive"))
      (node (ref "D2_10") (pin "2") (pinfunction "2_2") (pintype "passive"))
      (node (ref "D2_6") (pin "2") (pinfunction "2_2") (pintype "passive"))
      (node (ref "D3") (pin "1") (pinfunction "1_1") (pintype "passive"))
      (node (ref "D3_11") (pin "2") (pinfunction "2_2") (pintype "passive"))
      (node (ref "D3_7") (pin "2") (pinfunction "2_2") (pintype "passive"))
      (node (ref "D4_12") (pin "2") (pinfunction "2_2") (pintype "passive"))
      (node (ref "D5_13") (pin "2") (pinfunction "2_2") (pintype "passive"))
      (node (ref "D6_14") (pin "2") (pinfunction "2_2") (pintype "passive"))
      (node (ref "D7_15") (pin "2") (pinfunction "2_2") (pintype "passive"))
      (node (ref "EXPR") (pin "R") (pinfunction "R_R") (pintype "passive"))
      (node (ref "IC1") (pin "3") (pinfunction "W_3") (pintype "passive"))
      (node (ref "IC1") (pin "7") (pinfunction "HOLD_7") (pintype "passive"))
      (node (ref "IC1") (pin "8") (pinfunction "VCC_8") (pintype "power_in"))
      (node (ref "IC101") (pin "23") (pinfunction "DVD_23") (pintype "passive"))
      (node (ref "IC101") (pin "6") (pinfunction "AVD_6") (pintype "passive"))
      (node (ref "IC101") (pin "8") (pinfunction "DVD_8") (pintype "passive"))
      (node (ref "IC102") (pin "4") (pinfunction "VCC_4") (pintype "power_in"))
      (node (ref "IC2") (pin "5") (pinfunction "VCC_5") (pintype "passive"))
      (node (ref "IC3") (pin "24") (pinfunction "VDD_24") (pintype "passive"))
      (node (ref "IC5") (pin "16") (pinfunction "VDD_16") (pintype "passive"))
      (node (ref "K1") (pin "1") (pinfunction "+_1") (pintype "passive"))
      (node (ref "L1") (pin "2") (pinfunction "2_2") (pintype "passive"))
      (node (ref "OK1") (pin "6") (pinfunction "VCC_6") (pintype "passive"))
      (node (ref "POT0") (pin "3") (pinfunction "3_3") (pintype "passive"))
      (node (ref "POT1") (pin "3") (pinfunction "3_3") (pintype "passive"))
      (node (ref "POT2") (pin "3") (pinfunction "3_3") (pintype "passive"))
      (node (ref "POT3") (pin "3") (pinfunction "3_3") (pintype "passive"))
      (node (ref "PROG") (pin "5") (pinfunction "5_5") (pintype "passive"))
      (node (ref "PROG2") (pin "2") (pinfunction "2_2") (pintype "passive"))
      (node (ref "R104") (pin "2") (pinfunction "2_2") (pintype "passive"))
      (node (ref "R118") (pin "2") (pinfunction "2_2") (pintype "passive"))
      (node (ref "R4") (pin "2") (pinfunction "2_2") (pintype "passive"))
      (node (ref "R5") (pin "2") (pinfunction "2_2") (pintype "passive"))
      (node (ref "R7") (pin "1") (pinfunction "1_1") (pintype "passive"))
      (node (ref "R9") (pin "2") (pinfunction "2_2") (pintype "passive"))
      (node (ref "REG1") (pin "3") (pinfunction "OUTPUT_3") (pintype "power_in"))
      (node (ref "U1") (pin "17") (pinfunction "VCC_2_17") (pintype "passive"))
      (node (ref "U1") (pin "38") (pinfunction "VCC_3_38") (pintype "passive"))
      (node (ref "U1") (pin "5") (pinfunction "VCC_1_5") (pintype "passive"))
    )
    (net (code "2") (name "+9V") (class "Default")
      (node (ref "C1") (pin "+") (pinfunction "+_+") (pintype "passive"))
      (node (ref "C15") (pin "1") (pinfunction "1_1") (pintype "passive"))
      (node (ref "C2") (pin "1") (pinfunction "1_1") (pintype "passive"))
      (node (ref "D1") (pin "1") (pinfunction "1_1") (pintype "passive"))
      (node (ref "DC") (pin "1") (pinfunction "S_1") (pintype "passive"))
      (node (ref "IC6") (pin "9") (pinfunction "VDD_9") (pintype "power_in"))
      (node (ref "R115") (pin "1") (pinfunction "1_1") (pintype "passive"))
      (node (ref "REG1") (pin "1") (pinfunction "INPUT_1") (pintype "power_in"))
    )
    (net (code "3") (name "/A") (class "Default")
      (node (ref "IC6") (pin "1") (pinfunction "A_1") (pintype "passive"))
      (node (ref "R109") (pin "2") (pinfunction "2_2") (pintype "passive"))
      (node (ref "R110") (pin "1") (pinfunction "1_1") (pintype "passive"))
    )
    (net (code "4") (name "/AREF") (class "Default")
      (node (ref "U1") (pin "29") (pinfunction "AREF_29") (pintype "passive+no_connect"))
    )
    (net (code "5") (name "/AVCC") (class "Default")
      (node (ref "C8") (pin "1") (pinfunction "1_1") (pintype "passive"))
      (node (ref "L1") (pin "1") (pinfunction "1_1") (pintype "passive"))
      (node (ref "U1") (pin "27") (pinfunction "AVCC_27") (pintype "passive"))
    )
    (net (code "6") (name "/B") (class "Default")
      (node (ref "IC6") (pin "2") (pinfunction "B_2") (pintype "passive"))
      (node (ref "R107") (pin "2") (pinfunction "2_2") (pintype "passive"))
      (node (ref "R108") (pin "1") (pinfunction "1_1") (pintype "passive"))
    )
    (net (code "7") (name "/BYP_FSW0") (class "Default")
      (node (ref "FSW") (pin "1") (pinfunction "S_1") (pintype "passive"))
      (node (ref "U1") (pin "12") (pinfunction "(PCINT27/TXD1/INT1)_PD3_12") (pintype "passive"))
    )
    (net (code "8") (name "/BYP_K0") (class "Default")
      (node (ref "R12") (pin "1") (pinfunction "1_1") (pintype "passive"))
      (node (ref "U1") (pin "42") (pinfunction "PB2_(AIN0/INT2/PCINT10)_42") (pintype "passive"))
    )
    (net (code "9") (name "/BYP_LED0") (class "Default")
      (node (ref "R10") (pin "1") (pinfunction "1_1") (pintype "passive"))
      (node (ref "U1") (pin "11") (pinfunction "(PCINT26/RXD1/INT0)_PD2_11") (pintype "passive"))
    )
    (net (code "10") (name "/BYP_OK0") (class "Default")
      (node (ref "R11") (pin "1") (pinfunction "1_1") (pintype "passive"))
      (node (ref "U1") (pin "41") (pinfunction "PB1_(T1/CLKO/PCINT9)_41") (pintype "passive"))
    )
    (net (code "11") (name "/DPOT_LE0") (class "Default")
      (node (ref "IC6") (pin "5") (pinfunction "~{CS}_5") (pintype "input"))
      (node (ref "U1") (pin "43") (pinfunction "PB3_(AIN1/OC0A/PCINT11)_43") (pintype "passive"))
    )
    (net (code "12") (name "/EEPR_LE0") (class "Default")
      (node (ref "IC1") (pin "1") (pinfunction "S_1") (pintype "passive"))
      (node (ref "R5") (pin "1") (pinfunction "1_1") (pintype "passive"))
      (node (ref "U1") (pin "25") (pinfunction "PC6_(TOSC1/PCINT22)_25") (pintype "passive"))
    )
    (net (code "13") (name "/EXPR0_P") (class "Default")
      (node (ref "EXPR") (pin "SN") (pinfunction "SN_SN") (pintype "passive"))
      (node (ref "U1") (pin "26") (pinfunction "PC7_(TOSC2/PCINT23)_26") (pintype "passive"))
    )
    (net (code "14") (name "/EXPR0_W") (class "Default")
      (node (ref "EXPR") (pin "T") (pinfunction "T_T") (pintype "passive"))
      (node (ref "U1") (pin "35") (pinfunction "PA2_(ADC2/PCINT2)_35") (pintype "passive"))
    )
    (net (code "15") (name "/FV1_P0") (class "Default")
      (node (ref "IC101") (pin "20") (pinfunction "POT0_20") (pintype "passive"))
      (node (ref "U1") (pin "15") (pinfunction "(PCINT30/OC2B/ICP1)_PD6_15") (pintype "passive"))
    )
    (net (code "16") (name "/FV1_P1") (class "Default")
      (node (ref "IC101") (pin "21") (pinfunction "POT1_21") (pintype "passive"))
      (node (ref "U1") (pin "14") (pinfunction "(PCINT29/OC1A)_PD5_14") (pintype "passive"))
    )
    (net (code "17") (name "/FV1_P2") (class "Default")
      (node (ref "IC101") (pin "22") (pinfunction "POT2_22") (pintype "passive"))
      (node (ref "U1") (pin "13") (pinfunction "(PCINT28/XCK1/OC1B)_PD4_13") (pintype "passive"))
    )
    (net (code "18") (name "/FV1_RST") (class "Default")
      (node (ref "IC101") (pin "13") (pinfunction "T0_13") (pintype "passive"))
      (node (ref "PROG2") (pin "3") (pinfunction "3_3") (pintype "passive"))
      (node (ref "R118") (pin "1") (pinfunction "1_1") (pintype "passive"))
    )
    (net (code "19") (name "/FV1_S0") (class "Default")
      (node (ref "IC101") (pin "16") (pinfunction "S0_16") (pintype "passive"))
      (node (ref "U1") (pin "19") (pinfunction "(PCINT16/SCL)_PC0_19") (pintype "passive"))
    )
    (net (code "20") (name "/FV1_S1") (class "Default")
      (node (ref "IC101") (pin "17") (pinfunction "S1_17") (pintype "passive"))
      (node (ref "U1") (pin "20") (pinfunction "(PCINT17/SDA)_PC1_20") (pintype "passive"))
    )
    (net (code "21") (name "/FV1_S2") (class "Default")
      (node (ref "IC101") (pin "18") (pinfunction "S2_18") (pintype "passive"))
      (node (ref "U1") (pin "21") (pinfunction "(PCINT18/TCK)_PC2_21") (pintype "passive"))
    )
    (net (code "22") (name "/INPUT") (class "Default")
      (node (ref "INPUT") (pin "T") (pinfunction "T_T") (pintype "passive"))
      (node (ref "K1") (pin "6") (pinfunction "P_6") (pintype "passive"))
    )
    (net (code "23") (name "/MISO") (class "Default")
      (node (ref "IC1") (pin "2") (pinfunction "Q_2") (pintype "passive"))
      (node (ref "PROG") (pin "2") (pinfunction "2_2") (pintype "passive"))
      (node (ref "U1") (pin "2") (pinfunction "(PCINT14/OC3A/MISO)_PB6_2") (pintype "passive"))
    )
    (net (code "24") (name "/MOSI") (class "Default")
      (node (ref "IC1") (pin "5") (pinfunction "D_5") (pintype "passive"))
      (node (ref "IC3") (pin "2") (pinfunction "SDI_2") (pintype "passive"))
      (node (ref "IC5") (pin "2") (pinfunction "SDI_2") (pintype "passive"))
      (node (ref "IC6") (pin "7") (pinfunction "SDI_7") (pintype "passive"))
      (node (ref "PROG") (pin "3") (pinfunction "3_3") (pintype "passive"))
      (node (ref "U1") (pin "1") (pinfunction "(PCINT13/MOSI)_PB5_1") (pintype "passive"))
    )
    (net (code "25") (name "/OUTPUT") (class "Default")
      (node (ref "K1") (pin "3") (pinfunction "P_3") (pintype "passive"))
      (node (ref "OK2") (pin "6") (pinfunction "COL_6") (pintype "passive"))
      (node (ref "OUTPUT") (pin "T") (pinfunction "T_T") (pintype "passive"))
    )
    (net (code "26") (name "/P0_W") (class "Default")
      (node (ref "POT0") (pin "2") (pinfunction "2_2") (pintype "passive"))
      (node (ref "U1") (pin "34") (pinfunction "PA3_(ADC3/PCINT3)_34") (pintype "passive"))
    )
    (net (code "27") (name "/P1_W") (class "Default")
      (node (ref "POT1") (pin "2") (pinfunction "2_2") (pintype "passive"))
      (node (ref "U1") (pin "36") (pinfunction "PA1_(ADC1/PCINT1)_36") (pintype "passive"))
    )
    (net (code "28") (name "/P2_W") (class "Default")
      (node (ref "POT2") (pin "2") (pinfunction "2_2") (pintype "passive"))
      (node (ref "U1") (pin "33") (pinfunction "PA4_(ADC4/PCINT4)_33") (pintype "passive"))
    )
    (net (code "29") (name "/P3_W") (class "Default")
      (node (ref "POT3") (pin "2") (pinfunction "2_2") (pintype "passive"))
      (node (ref "U1") (pin "37") (pinfunction "PA0_(ADC0/PCINT0)_37") (pintype "passive"))
    )
    (net (code "30") (name "/PS_0") (class "Default")
      (node (ref "D0_8") (pin "1") (pinfunction "1_1") (pintype "passive"))
      (node (ref "IC3") (pin "12") (pinfunction "OUT7_12") (pintype "passive"))
    )
    (net (code "31") (name "/PS_1") (class "Default")
      (node (ref "D1_9") (pin "1") (pinfunction "1_1") (pintype "passive"))
      (node (ref "IC3") (pin "11") (pinfunction "OUT6_11") (pintype "passive"))
    )
    (net (code "32") (name "/PS_2") (class "Default")
      (node (ref "D2_10") (pin "1") (pinfunction "1_1") (pintype "passive"))
      (node (ref "IC3") (pin "10") (pinfunction "OUT5_10") (pintype "passive"))
    )
    (net (code "33") (name "/PS_3") (class "Default")
      (node (ref "D3_11") (pin "1") (pinfunction "1_1") (pintype "passive"))
      (node (ref "IC3") (pin "9") (pinfunction "OUT4_9") (pintype "passive"))
    )
    (net (code "34") (name "/PS_4") (class "Default")
      (node (ref "D4_12") (pin "1") (pinfunction "1_1") (pintype "passive"))
      (node (ref "IC3") (pin "8") (pinfunction "OUT3_8") (pintype "passive"))
    )
    (net (code "35") (name "/PS_5") (class "Default")
      (node (ref "D5_13") (pin "1") (pinfunction "1_1") (pintype "passive"))
      (node (ref "IC3") (pin "7") (pinfunction "OUT2_7") (pintype "passive"))
    )
    (net (code "36") (name "/PS_6") (class "Default")
      (node (ref "D6_14") (pin "1") (pinfunction "1_1") (pintype "passive"))
      (node (ref "IC3") (pin "6") (pinfunction "OUT1_6") (pintype "passive"))
    )
    (net (code "37") (name "/PS_7") (class "Default")
      (node (ref "D7_15") (pin "1") (pinfunction "1_1") (pintype "passive"))
      (node (ref "IC3") (pin "5") (pinfunction "OUT0_5") (pintype "passive"))
    )
    (net (code "38") (name "/PS_8") (class "Default")
      (node (ref "D7_15") (pin "3") (pinfunction "3_3") (pintype "passive"))
      (node (ref "IC3") (pin "20") (pinfunction "OUT15_20") (pintype "passive"))
    )
    (net (code "39") (name "/PS_9") (class "Default")
      (node (ref "D6_14") (pin "3") (pinfunction "3_3") (pintype "passive"))
      (node (ref "IC3") (pin "19") (pinfunction "OUT14_19") (pintype "passive"))
    )
    (net (code "40") (name "/PS_10") (class "Default")
      (node (ref "D5_13") (pin "3") (pinfunction "3_3") (pintype "passive"))
      (node (ref "IC3") (pin "18") (pinfunction "OUT13_18") (pintype "passive"))
    )
    (net (code "41") (name "/PS_11") (class "Default")
      (node (ref "D4_12") (pin "3") (pinfunction "3_3") (pintype "passive"))
      (node (ref "IC3") (pin "17") (pinfunction "OUT12_17") (pintype "passive"))
    )
    (net (code "42") (name "/PS_12") (class "Default")
      (node (ref "D3_11") (pin "3") (pinfunction "3_3") (pintype "passive"))
      (node (ref "IC3") (pin "16") (pinfunction "OUT11_16") (pintype "passive"))
    )
    (net (code "43") (name "/PS_13") (class "Default")
      (node (ref "D2_10") (pin "3") (pinfunction "3_3") (pintype "passive"))
      (node (ref "IC3") (pin "15") (pinfunction "OUT10_15") (pintype "passive"))
    )
    (net (code "44") (name "/PS_14") (class "Default")
      (node (ref "D1_9") (pin "3") (pinfunction "3_3") (pintype "passive"))
      (node (ref "IC3") (pin "14") (pinfunction "OUT9_14") (pintype "passive"))
    )
    (net (code "45") (name "/PS_15") (class "Default")
      (node (ref "D0_8") (pin "3") (pinfunction "3_3") (pintype "passive"))
      (node (ref "IC3") (pin "13") (pinfunction "OUT8_13") (pintype "passive"))
    )
    (net (code "46") (name "/PS_ENC_A") (class "Default")
      (node (ref "S1") (pin "1") (pinfunction "A_1") (pintype "passive"))
      (node (ref "U1") (pin "32") (pinfunction "PA5_(ADC5/PCINT5)_32") (pintype "passive"))
    )
    (net (code "47") (name "/PS_ENC_B") (class "Default")
      (node (ref "S1") (pin "3") (pinfunction "B_3") (pintype "passive"))
      (node (ref "U1") (pin "31") (pinfunction "PA6_(ADC6/PCINT6)_31") (pintype "passive"))
    )
    (net (code "48") (name "/PS_ENC_SW") (class "Default")
      (node (ref "S1") (pin "4") (pinfunction "4_4") (pintype "passive"))
      (node (ref "U1") (pin "30") (pinfunction "PA7_(ADC7/PCINT7)_30") (pintype "passive"))
    )
    (net (code "49") (name "/PS_LE0") (class "Default")
      (node (ref "IC3") (pin "4") (pinfunction "LE_4") (pintype "passive"))
      (node (ref "U1") (pin "23") (pinfunction "PC4_(TDO/PCINT20)_23") (pintype "passive"))
    )
    (net (code "50") (name "/RESET") (class "Default")
      (node (ref "PROG") (pin "4") (pinfunction "4_4") (pintype "passive"))
      (node (ref "R4") (pin "1") (pinfunction "1_1") (pintype "passive"))
      (node (ref "U1") (pin "4") (pinfunction "RESET_4") (pintype "passive"))
    )
    (net (code "51") (name "/RETURN") (class "Default")
      (node (ref "C114") (pin "1") (pinfunction "1_1") (pintype "passive"))
      (node (ref "K1") (pin "4") (pinfunction "S_4") (pintype "passive"))
      (node (ref "R114") (pin "2") (pinfunction "2_2") (pintype "passive"))
    )
    (net (code "52") (name "/RX0") (class "Default")
      (node (ref "IC2") (pin "2") (pinfunction "A_2") (pintype "passive"))
      (node (ref "OK1") (pin "5") (pinfunction "VO_5") (pintype "passive"))
      (node (ref "R7") (pin "2") (pinfunction "2_2") (pintype "passive"))
      (node (ref "U1") (pin "9") (pinfunction "(PCINT24/RXD0/T3)_PD0_9") (pintype "passive"))
    )
    (net (code "53") (name "/SCK") (class "Default")
      (node (ref "IC1") (pin "6") (pinfunction "C_6") (pintype "passive"))
      (node (ref "IC3") (pin "3") (pinfunction "CLK_3") (pintype "passive"))
      (node (ref "IC5") (pin "3") (pinfunction "CLK_3") (pintype "passive"))
      (node (ref "IC6") (pin "6") (pinfunction "CLK_6") (pintype "input"))
      (node (ref "PROG") (pin "1") (pinfunction "1_1") (pintype "passive"))
      (node (ref "U1") (pin "3") (pinfunction "(PCINT15/OC3B/SCK)_PB7_3") (pintype "passive"))
    )
    (net (code "54") (name "/SCL") (class "Default")
      (node (ref "IC101") (pin "14") (pinfunction "SCK_14") (pintype "passive"))
      (node (ref "IC102") (pin "1") (pinfunction "SCL_1") (pintype "passive"))
      (node (ref "PROG2") (pin "4") (pinfunction "4_4") (pintype "passive"))
    )
    (net (code "55") (name "/SDA") (class "Default")
      (node (ref "IC101") (pin "15") (pinfunction "SDA_15") (pintype "passive"))
      (node (ref "IC102") (pin "3") (pinfunction "SDA_3") (pintype "passive"))
      (node (ref "PROG2") (pin "5") (pinfunction "5_5") (pintype "passive"))
    )
    (net (code "56") (name "/SEND") (class "Default")
      (node (ref "C100") (pin "2") (pinfunction "2_2") (pintype "passive"))
      (node (ref "K1") (pin "5") (pinfunction "S_5") (pintype "passive"))
      (node (ref "R100") (pin "2") (pinfunction "2_2") (pintype "passive"))
    )
    (net (code "57") (name "/TAP_0") (class "Default")
      (node (ref "D0_4") (pin "1") (pinfunction "1_1") (pintype "passive"))
      (node (ref "IC5") (pin "5") (pinfunction "OUT0_5") (pintype "passive"))
    )
    (net (code "58") (name "/TAP_1") (class "Default")
      (node (ref "D1_5") (pin "1") (pinfunction "1_1") (pintype "passive"))
      (node (ref "IC5") (pin "6") (pinfunction "OUT1_6") (pintype "passive"))
    )
    (net (code "59") (name "/TAP_2") (class "Default")
      (node (ref "D2_6") (pin "1") (pinfunction "1_1") (pintype "passive"))
      (node (ref "IC5") (pin "7") (pinfunction "OUT2_7") (pintype "passive"))
    )
    (net (code "60") (name "/TAP_3") (class "Default")
      (node (ref "D3_7") (pin "1") (pinfunction "1_1") (pintype "passive"))
      (node (ref "IC5") (pin "8") (pinfunction "OUT3_8") (pintype "passive"))
    )
    (net (code "61") (name "/TAP_4") (class "Default")
      (node (ref "D0_4") (pin "3") (pinfunction "3_3") (pintype "passive"))
      (node (ref "IC5") (pin "9") (pinfunction "OUT4_9") (pintype "passive"))
    )
    (net (code "62") (name "/TAP_5") (class "Default")
      (node (ref "D1_5") (pin "3") (pinfunction "3_3") (pintype "passive"))
      (node (ref "IC5") (pin "10") (pinfunction "OUT5_10") (pintype "passive"))
    )
    (net (code "63") (name "/TAP_6") (class "Default")
      (node (ref "D2_6") (pin "3") (pinfunction "3_3") (pintype "passive"))
      (node (ref "IC5") (pin "11") (pinfunction "OUT6_11") (pintype "passive"))
    )
    (net (code "64") (name "/TAP_7") (class "Default")
      (node (ref "D3_7") (pin "3") (pinfunction "3_3") (pintype "passive"))
      (node (ref "IC5") (pin "12") (pinfunction "OUT7_12") (pintype "passive"))
    )
    (net (code "65") (name "/TAP_FSW0") (class "Default")
      (node (ref "TAPFSW") (pin "2") (pinfunction "S_2") (pintype "passive"))
      (node (ref "U1") (pin "22") (pinfunction "(PCINT19/TMS)_PC3_22") (pintype "passive"))
    )
    (net (code "66") (name "/TAP_LE0") (class "Default")
      (node (ref "IC5") (pin "4") (pinfunction "LE_4") (pintype "passive"))
      (node (ref "U1") (pin "24") (pinfunction "PC5_(TDI/PCINT21)_24") (pintype "passive"))
    )
    (net (code "67") (name "/TAP_LED0") (class "Default")
      (node (ref "R15") (pin "1") (pinfunction "1_1") (pintype "passive"))
      (node (ref "U1") (pin "16") (pinfunction "(PCINT31/OC2A)_PD7_16") (pintype "passive"))
    )
    (net (code "68") (name "/TX0") (class "Default")
      (node (ref "U1") (pin "10") (pinfunction "(PCINT25/TXD0)_PD1_10") (pintype "passive"))
      (node (ref "UART") (pin "1") (pinfunction "1_1") (pintype "passive"))
    )
    (net (code "69") (name "/XTAL1") (class "Default")
      (node (ref "U1") (pin "8") (pinfunction "XTAL1_8") (pintype "passive+no_connect"))
    )
    (net (code "70") (name "/XTAL2") (class "Default")
      (node (ref "U1") (pin "7") (pinfunction "XTAL2_7") (pintype "passive+no_connect"))
    )
    (net (code "71") (name "GND") (class "Default")
      (node (ref "BYPLED") (pin "2") (pinfunction "S_2") (pintype "passive"))
      (node (ref "C1") (pin "-") (pinfunction "-_-") (pintype "passive"))
      (node (ref "C10") (pin "2") (pinfunction "2_2") (pintype "passive"))
      (node (ref "C102") (pin "2") (pinfunction "2_2") (pintype "passive"))
      (node (ref "C103") (pin "1") (pinfunction "1_1") (pintype "passive"))
      (node (ref "C104") (pin "2") (pinfunction "2_2") (pintype "passive"))
      (node (ref "C105") (pin "2") (pinfunction "2_2") (pintype "passive"))
      (node (ref "C106") (pin "2") (pinfunction "2_2") (pintype "passive"))
      (node (ref "C107") (pin "2") (pinfunction "2_2") (pintype "passive"))
      (node (ref "C109") (pin "2") (pinfunction "2_2") (pintype "passive"))
      (node (ref "C11") (pin "2") (pinfunction "2_2") (pintype "passive"))
      (node (ref "C115") (pin "-") (pinfunction "-_-") (pintype "passive"))
      (node (ref "C116") (pin "-") (pinfunction "-_-") (pintype "passive"))
      (node (ref "C117") (pin "2") (pinfunction "2_2") (pintype "passive"))
      (node (ref "C12") (pin "1") (pinfunction "1_1") (pintype "passive"))
      (node (ref "C13") (pin "2") (pinfunction "2_2") (pintype "passive"))
      (node (ref "C14") (pin "2") (pinfunction "2_2") (pintype "passive"))
      (node (ref "C15") (pin "2") (pinfunction "2_2") (pintype "passive"))
      (node (ref "C2") (pin "2") (pinfunction "2_2") (pintype "passive"))
      (node (ref "C3") (pin "2") (pinfunction "2_2") (pintype "passive"))
      (node (ref "C4") (pin "-") (pinfunction "-_-") (pintype "passive"))
      (node (ref "C5") (pin "2") (pinfunction "2_2") (pintype "passive"))
      (node (ref "C6") (pin "2") (pinfunction "2_2") (pintype "passive"))
      (node (ref "C7") (pin "2") (pinfunction "2_2") (pintype "passive"))
      (node (ref "C8") (pin "2") (pinfunction "2_2") (pintype "passive"))
      (node (ref "C9") (pin "1") (pinfunction "1_1") (pintype "passive"))
      (node (ref "D1") (pin "2") (pinfunction "2_2") (pintype "passive"))
      (node (ref "DC") (pin "2") (pinfunction "S_2") (pintype "passive"))
      (node (ref "EXPR") (pin "S") (pinfunction "S_S") (pintype "passive"))
      (node (ref "FSW") (pin "2") (pinfunction "S_2") (pintype "passive"))
      (node (ref "IC1") (pin "4") (pinfunction "VSS_4") (pintype "power_in"))
      (node (ref "IC100") (pin "11") (pinfunction "V-_11") (pintype "power_in"))
      (node (ref "IC101") (pin "11") (pinfunction "GND_11") (pintype "passive"))
      (node (ref "IC101") (pin "12") (pinfunction "T1_12") (pintype "passive"))
      (node (ref "IC101") (pin "19") (pinfunction "GND_19") (pintype "passive"))
      (node (ref "IC101") (pin "24") (pinfunction "GND_24") (pintype "passive"))
      (node (ref "IC101") (pin "25") (pinfunction "REFN_25") (pintype "passive"))
      (node (ref "IC101") (pin "4") (pinfunction "GND_4") (pintype "passive"))
      (node (ref "IC101") (pin "7") (pinfunction "GND_7") (pintype "passive"))
      (node (ref "IC102") (pin "2") (pinfunction "VSS_2") (pintype "power_in"))
      (node (ref "IC102") (pin "5") (pinfunction "WP_5") (pintype "passive"))
      (node (ref "IC2") (pin "3") (pinfunction "GND_3") (pintype "passive"))
      (node (ref "IC3") (pin "1") (pinfunction "GND_1") (pintype "passive"))
      (node (ref "IC3") (pin "21") (pinfunction "~{OE}_21") (pintype "passive"))
      (node (ref "IC5") (pin "1") (pinfunction "GND_1") (pintype "passive"))
      (node (ref "IC5") (pin "13") (pinfunction "~{OE}_13") (pintype "passive"))
      (node (ref "IC6") (pin "3") (pinfunction "VSS_3") (pintype "power_in"))
      (node (ref "IC6") (pin "4") (pinfunction "GND_4") (pintype "power_in"))
      (node (ref "INPUT") (pin "S") (pinfunction "S_S") (pintype "passive"))
      (node (ref "MIDI_THRU") (pin "S") (pinfunction "S_S") (pintype "passive"))
      (node (ref "OK1") (pin "4") (pinfunction "GND_4") (pintype "passive"))
      (node (ref "OK2") (pin "3") (pinfunction "C_3") (pintype "passive"))
      (node (ref "OK2") (pin "4") (pinfunction "EMIT_4") (pintype "passive"))
      (node (ref "OUTPUT") (pin "S") (pinfunction "S_S") (pintype "passive"))
      (node (ref "POT0") (pin "1") (pinfunction "1_1") (pintype "passive"))
      (node (ref "POT1") (pin "1") (pinfunction "1_1") (pintype "passive"))
      (node (ref "POT2") (pin "1") (pinfunction "1_1") (pintype "passive"))
      (node (ref "POT3") (pin "1") (pinfunction "1_1") (pintype "passive"))
      (node (ref "PROG") (pin "6") (pinfunction "6_6") (pintype "passive"))
      (node (ref "PROG2") (pin "1") (pinfunction "1_1") (pintype "passive"))
      (node (ref "Q1") (pin "2") (pinfunction "E_2") (pintype "passive"))
      (node (ref "R100") (pin "1") (pinfunction "1_1") (pintype "passive"))
      (node (ref "R114") (pin "1") (pinfunction "1_1") (pintype "passive"))
      (node (ref "R117") (pin "1") (pinfunction "1_1") (pintype "passive"))
      (node (ref "R13") (pin "1") (pinfunction "1_1") (pintype "passive"))
      (node (ref "R14") (pin "1") (pinfunction "1_1") (pintype "passive"))
      (node (ref "REG1") (pin "2") (pinfunction "COMMON_2") (pintype "power_in"))
      (node (ref "S1") (pin "2") (pinfunction "C_2") (pintype "passive"))
      (node (ref "S1") (pin "5") (pinfunction "5_5") (pintype "passive"))
      (node (ref "TAPFSW") (pin "1") (pinfunction "S_1") (pintype "passive"))
      (node (ref "TAPLED") (pin "2") (pinfunction "S_2") (pintype "passive"))
      (node (ref "U1") (pin "18") (pinfunction "GND_2_18") (pintype "passive"))
      (node (ref "U1") (pin "28") (pinfunction "GND_3_28") (pintype "passive"))
      (node (ref "U1") (pin "39") (pinfunction "GND_4_39") (pintype "passive"))
      (node (ref "U1") (pin "6") (pinfunction "GND_1_6") (pintype "passive"))
    )
    (net (code "72") (name "Net-(BYPLEDB-S)") (class "Default")
      (node (ref "BYPLED") (pin "1") (pinfunction "S_1") (pintype "passive"))
      (node (ref "BYP_BRIGHT") (pin "2") (pinfunction "2_2") (pintype "passive"))
      (node (ref "BYP_BRIGHT") (pin "3") (pinfunction "3_3") (pintype "passive"))
    )
    (net (code "73") (name "Net-(BYP_BRIGHT-Pad1)") (class "Default")
      (node (ref "BYP_BRIGHT") (pin "1") (pinfunction "1_1") (pintype "passive"))
      (node (ref "R10") (pin "2") (pinfunction "2_2") (pintype "passive"))
    )
    (net (code "74") (name "Net-(C10-Pad1)") (class "Default")
      (node (ref "C10") (pin "1") (pinfunction "1_1") (pintype "passive"))
      (node (ref "MIDI_IN") (pin "S") (pinfunction "S_S") (pintype "passive"))
    )
    (net (code "75") (name "Net-(C100-Pad1)") (class "Default")
      (node (ref "C100") (pin "1") (pinfunction "1_1") (pintype "passive"))
      (node (ref "R101") (pin "1") (pinfunction "1_1") (pintype "passive"))
    )
    (net (code "76") (name "Net-(C101-Pad1)") (class "Default")
      (node (ref "C101") (pin "1") (pinfunction "1_1") (pintype "passive"))
      (node (ref "R103") (pin "1") (pinfunction "1_1") (pintype "passive"))
    )
    (net (code "77") (name "Net-(C108-Pad1)") (class "Default")
      (node (ref "C108") (pin "1") (pinfunction "1_1") (pintype "passive"))
      (node (ref "R105") (pin "1") (pinfunction "1_1") (pintype "passive"))
    )
    (net (code "78") (name "Net-(C110-Pad1)") (class "Default")
      (node (ref "C110") (pin "1") (pinfunction "1_1") (pintype "passive"))
      (node (ref "R107") (pin "1") (pinfunction "1_1") (pintype "passive"))
    )
    (net (code "79") (name "Net-(C111-Pad1)") (class "Default")
      (node (ref "C111") (pin "1") (pinfunction "1_1") (pintype "passive"))
      (node (ref "R109") (pin "1") (pinfunction "1_1") (pintype "passive"))
    )
    (net (code "80") (name "Net-(C114-Pad2)") (class "Default")
      (node (ref "C114") (pin "2") (pinfunction "2_2") (pintype "passive"))
      (node (ref "R113") (pin "2") (pinfunction "2_2") (pintype "passive"))
    )
    (net (code "81") (name "Net-(DIV_BRIGHT-Pad1)") (class "Default")
      (node (ref "DIV_BRIGHT") (pin "1") (pinfunction "1_1") (pintype "passive"))
      (node (ref "R14") (pin "2") (pinfunction "2_2") (pintype "passive"))
    )
    (net (code "82") (name "Net-(IC2-Y)") (class "Default")
      (node (ref "IC2") (pin "4") (pinfunction "Y_4") (pintype "passive"))
      (node (ref "R8") (pin "1") (pinfunction "1_1") (pintype "passive"))
    )
    (net (code "83") (name "Net-(IC3-R-EXT)") (class "Default")
      (node (ref "IC3") (pin "23") (pinfunction "R-EXT_23") (pintype "passive"))
      (node (ref "PS_BRIGHT") (pin "2") (pinfunction "2_2") (pintype "passive"))
      (node (ref "PS_BRIGHT") (pin "3") (pinfunction "3_3") (pintype "passive"))
    )
    (net (code "84") (name "Net-(IC5-R-EXT)") (class "Default")
      (node (ref "DIV_BRIGHT") (pin "2") (pinfunction "2_2") (pintype "passive"))
      (node (ref "DIV_BRIGHT") (pin "3") (pinfunction "3_3") (pintype "passive"))
      (node (ref "IC5") (pin "15") (pinfunction "R-EXT_15") (pintype "passive"))
    )
    (net (code "85") (name "Net-(IC100A-+IN)") (class "Default")
      (node (ref "C109") (pin "1") (pinfunction "1_1") (pintype "passive"))
      (node (ref "IC100") (pin "3") (pinfunction "+IN_3") (pintype "passive"))
      (node (ref "R105") (pin "2") (pinfunction "2_2") (pintype "passive"))
      (node (ref "R106") (pin "1") (pinfunction "1_1") (pintype "passive"))
    )
    (net (code "86") (name "Net-(IC100A--IN)") (class "Default")
      (node (ref "C111") (pin "2") (pinfunction "2_2") (pintype "passive"))
      (node (ref "IC100") (pin "1") (pinfunction "OUT_1") (pintype "output"))
      (node (ref "IC100") (pin "2") (pinfunction "-IN_2") (pintype "passive"))
    )
    (net (code "87") (name "Net-(IC100B--IN)") (class "Default")
      (node (ref "C112") (pin "2") (pinfunction "2_2") (pintype "passive"))
      (node (ref "IC100") (pin "6") (pinfunction "-IN_6") (pintype "passive"))
      (node (ref "R108") (pin "2") (pinfunction "2_2") (pintype "passive"))
      (node (ref "R110") (pin "2") (pinfunction "2_2") (pintype "passive"))
      (node (ref "VOLUME") (pin "1") (pinfunction "1_1") (pintype "passive"))
    )
    (net (code "88") (name "Net-(IC100B-OUT)") (class "Default")
      (node (ref "C112") (pin "1") (pinfunction "1_1") (pintype "passive"))
      (node (ref "IC100") (pin "7") (pinfunction "OUT_7") (pintype "output"))
      (node (ref "R111") (pin "1") (pinfunction "1_1") (pintype "passive"))
      (node (ref "VOLUME") (pin "2") (pinfunction "2_2") (pintype "passive"))
      (node (ref "VOLUME") (pin "3") (pinfunction "3_3") (pintype "passive"))
    )
    (net (code "89") (name "Net-(IC100C--IN)") (class "Default")
      (node (ref "C113") (pin "2") (pinfunction "2_2") (pintype "passive"))
      (node (ref "IC100") (pin "9") (pinfunction "-IN_9") (pintype "passive"))
      (node (ref "R111") (pin "2") (pinfunction "2_2") (pintype "passive"))
      (node (ref "R112") (pin "1") (pinfunction "1_1") (pintype "passive"))
    )
    (net (code "90") (name "Net-(IC100C-OUT)") (class "Default")
      (node (ref "C113") (pin "1") (pinfunction "1_1") (pintype "passive"))
      (node (ref "IC100") (pin "8") (pinfunction "OUT_8") (pintype "output"))
      (node (ref "R112") (pin "2") (pinfunction "2_2") (pintype "passive"))
      (node (ref "R113") (pin "1") (pinfunction "1_1") (pintype "passive"))
    )
    (net (code "91") (name "Net-(IC100D-+IN)") (class "Default")
      (node (ref "IC100") (pin "12") (pinfunction "+IN_12") (pintype "passive"))
      (node (ref "R101") (pin "2") (pinfunction "2_2") (pintype "passive"))
      (node (ref "R102") (pin "1") (pinfunction "1_1") (pintype "passive"))
    )
    (net (code "92") (name "Net-(IC100D--IN)") (class "Default")
      (node (ref "C101") (pin "2") (pinfunction "2_2") (pintype "passive"))
      (node (ref "C110") (pin "2") (pinfunction "2_2") (pintype "passive"))
      (node (ref "IC100") (pin "13") (pinfunction "-IN_13") (pintype "passive"))
      (node (ref "IC100") (pin "14") (pinfunction "OUT_14") (pintype "output"))
    )
    (net (code "93") (name "Net-(IC101-LIN)") (class "Default")
      (node (ref "C102") (pin "1") (pinfunction "1_1") (pintype "passive"))
      (node (ref "IC101") (pin "1") (pinfunction "LIN_1") (pintype "passive"))
      (node (ref "IC101") (pin "2") (pinfunction "RIN_2") (pintype "passive"))
      (node (ref "R103") (pin "2") (pinfunction "2_2") (pintype "passive"))
    )
    (net (code "94") (name "Net-(IC101-LOUT)") (class "Default")
      (node (ref "C108") (pin "2") (pinfunction "2_2") (pintype "passive"))
      (node (ref "IC101") (pin "28") (pinfunction "LOUT_28") (pintype "passive"))
    )
    (net (code "95") (name "Net-(IC101-MID)") (class "Default")
      (node (ref "C103") (pin "2") (pinfunction "2_2") (pintype "passive"))
      (node (ref "IC101") (pin "3") (pinfunction "MID_3") (pintype "passive"))
    )
    (net (code "96") (name "Net-(IC101-REFP)") (class "Default")
      (node (ref "C106") (pin "1") (pinfunction "1_1") (pintype "passive"))
      (node (ref "IC101") (pin "26") (pinfunction "REFP_26") (pintype "passive"))
      (node (ref "R104") (pin "1") (pinfunction "1_1") (pintype "passive"))
    )
    (net (code "97") (name "Net-(IC101-X1)") (class "Default")
      (node (ref "IC101") (pin "10") (pinfunction "X1_10") (pintype "passive"))
      (node (ref "Y100") (pin "2") (pinfunction "2_2") (pintype "passive"))
    )
    (net (code "98") (name "Net-(IC101-X2)") (class "Default")
      (node (ref "C104") (pin "1") (pinfunction "1_1") (pintype "passive"))
      (node (ref "IC101") (pin "9") (pinfunction "X2_9") (pintype "passive"))
      (node (ref "Y100") (pin "1") (pinfunction "1_1") (pintype "passive"))
    )
    (net (code "99") (name "Net-(K1A--)") (class "Default")
      (node (ref "D3") (pin "2") (pinfunction "2_2") (pintype "passive"))
      (node (ref "K1") (pin "8") (pinfunction "-_8") (pintype "passive"))
      (node (ref "Q1") (pin "3") (pinfunction "C_3") (pintype "passive"))
    )
    (net (code "100") (name "Net-(K1B-O)") (class "Default")
      (node (ref "K1") (pin "2") (pinfunction "O_2") (pintype "passive"))
      (node (ref "K1") (pin "7") (pinfunction "O_7") (pintype "passive"))
    )
    (net (code "101") (name "Net-(MIDI_IN-PadR)") (class "Default")
      (node (ref "MIDI_IN") (pin "R") (pinfunction "R_R") (pintype "passive"))
      (node (ref "R6") (pin "1") (pinfunction "1_1") (pintype "passive"))
    )
    (net (code "102") (name "Net-(MIDI_THRU-PadR)") (class "Default")
      (node (ref "MIDI_THRU") (pin "R") (pinfunction "R_R") (pintype "passive"))
      (node (ref "R9") (pin "1") (pinfunction "1_1") (pintype "passive"))
    )
    (net (code "103") (name "Net-(MIDI_THRU-PadT)") (class "Default")
      (node (ref "MIDI_THRU") (pin "T") (pinfunction "T_T") (pintype "passive"))
      (node (ref "R8") (pin "2") (pinfunction "2_2") (pintype "passive"))
    )
    (net (code "104") (name "Net-(OK1-A)") (class "Default")
      (node (ref "D2") (pin "1") (pinfunction "1_1") (pintype "passive"))
      (node (ref "OK1") (pin "1") (pinfunction "A_1") (pintype "passive"))
      (node (ref "R6") (pin "2") (pinfunction "2_2") (pintype "passive"))
    )
    (net (code "105") (name "Net-(OK1-K)") (class "Default")
      (node (ref "D2") (pin "2") (pinfunction "2_2") (pintype "passive"))
      (node (ref "MIDI_IN") (pin "T") (pinfunction "T_T") (pintype "passive"))
      (node (ref "OK1") (pin "3") (pinfunction "K_3") (pintype "passive"))
    )
    (net (code "106") (name "Net-(OK2-A)") (class "Default")
      (node (ref "OK2") (pin "1") (pinfunction "A_1") (pintype "passive"))
      (node (ref "R11") (pin "2") (pinfunction "2_2") (pintype "passive"))
    )
    (net (code "107") (name "Net-(PS_BRIGHT-Pad1)") (class "Default")
      (node (ref "PS_BRIGHT") (pin "1") (pinfunction "1_1") (pintype "passive"))
      (node (ref "R13") (pin "2") (pinfunction "2_2") (pintype "passive"))
    )
    (net (code "108") (name "Net-(Q1-B)") (class "Default")
      (node (ref "Q1") (pin "1") (pinfunction "B_1") (pintype "passive"))
      (node (ref "R12") (pin "2") (pinfunction "2_2") (pintype "passive"))
    )
    (net (code "109") (name "Net-(R15-Pad2)") (class "Default")
      (node (ref "R15") (pin "2") (pinfunction "2_2") (pintype "passive"))
      (node (ref "TAP_BRIGHT") (pin "1") (pinfunction "1_1") (pintype "passive"))
    )
    (net (code "110") (name "Net-(TAPLEDB-S)") (class "Default")
      (node (ref "TAPLED") (pin "1") (pinfunction "S_1") (pintype "passive"))
      (node (ref "TAP_BRIGHT") (pin "2") (pinfunction "2_2") (pintype "passive"))
      (node (ref "TAP_BRIGHT") (pin "3") (pinfunction "3_3") (pintype "passive"))
    )
    (net (code "111") (name "Vb") (class "Default")
      (node (ref "C116") (pin "+") (pinfunction "+_+") (pintype "passive"))
      (node (ref "IC100") (pin "10") (pinfunction "+IN_10") (pintype "passive"))
      (node (ref "IC100") (pin "5") (pinfunction "+IN_5") (pintype "passive"))
      (node (ref "IC6") (pin "10") (pinfunction "W_10") (pintype "passive"))
      (node (ref "R102") (pin "2") (pinfunction "2_2") (pintype "passive"))
      (node (ref "R106") (pin "2") (pinfunction "2_2") (pintype "passive"))
      (node (ref "R116") (pin "2") (pinfunction "2_2") (pintype "passive"))
      (node (ref "R117") (pin "2") (pinfunction "2_2") (pintype "passive"))
    )
    (net (code "112") (name "Vr") (class "Default")
      (node (ref "C115") (pin "+") (pinfunction "+_+") (pintype "passive"))
      (node (ref "C117") (pin "1") (pinfunction "1_1") (pintype "passive"))
      (node (ref "IC100") (pin "4") (pinfunction "V+_4") (pintype "power_in"))
      (node (ref "R115") (pin "2") (pinfunction "2_2") (pintype "passive"))
      (node (ref "R116") (pin "1") (pinfunction "1_1") (pintype "passive"))
    )
    (net (code "113") (name "unconnected-(IC2-NC-Pad1)") (class "Default")
      (node (ref "IC2") (pin "1") (pinfunction "NC_1") (pintype "passive"))
    )
    (net (code "114") (name "unconnected-(IC3-SDO-Pad22)") (class "Default")
      (node (ref "IC3") (pin "22") (pinfunction "SDO_22") (pintype "passive"))
    )
    (net (code "115") (name "unconnected-(IC5-SDO-Pad14)") (class "Default")
      (node (ref "IC5") (pin "14") (pinfunction "SDO_14") (pintype "passive"))
    )
    (net (code "116") (name "unconnected-(IC6-SDO-Pad8)") (class "Default")
      (node (ref "IC6") (pin "8") (pinfunction "SDO_8") (pintype "passive"))
    )
    (net (code "117") (name "unconnected-(IC101-CLIP-Pad5)") (class "Default")
      (node (ref "IC101") (pin "5") (pinfunction "CLIP_5") (pintype "passive+no_connect"))
    )
    (net (code "118") (name "unconnected-(IC101-ROUT-Pad27)") (class "Default")
      (node (ref "IC101") (pin "27") (pinfunction "ROUT_27") (pintype "passive+no_connect"))
    )
    (net (code "119") (name "unconnected-(INPUT-PadR)") (class "Default")
      (node (ref "INPUT") (pin "R") (pinfunction "R_R") (pintype "passive+no_connect"))
    )
    (net (code "120") (name "unconnected-(INPUT-PadSN)") (class "Default")
      (node (ref "INPUT") (pin "SN") (pinfunction "SN_SN") (pintype "passive+no_connect"))
    )
    (net (code "121") (name "unconnected-(OUTPUT-PadR)") (class "Default")
      (node (ref "OUTPUT") (pin "R") (pinfunction "R_R") (pintype "passive+no_connect"))
    )
    (net (code "122") (name "unconnected-(OUTPUT-PadSN)") (class "Default")
      (node (ref "OUTPUT") (pin "SN") (pinfunction "SN_SN") (pintype "passive+no_connect"))
    )
    (net (code "123") (name "unconnected-(U1-PB0_(XCK0{slash}T0{slash}PCINT8)-Pad40)") (class "Default")
      (node (ref "U1") (pin "40") (pinfunction "PB0_(XCK0/T0/PCINT8)_40") (pintype "passive"))
    )
    (net (code "124") (name "unconnected-(U1-PB4_(SS{slash}OC0B{slash}PCINT12)-Pad44)") (class "Default")
      (node (ref "U1") (pin "44") (pinfunction "PB4_(SS/OC0B/PCINT12)_44") (pintype "passive"))
    )
    (net (code "125") (name "unconnected-(UART-Pad2)") (class "Default")
      (node (ref "UART") (pin "2") (pinfunction "2_2") (pintype "passive+no_connect"))
    )
  )
)
